# inverter_module.net
KiCad netlist of a schematic drawn in Altium Designer
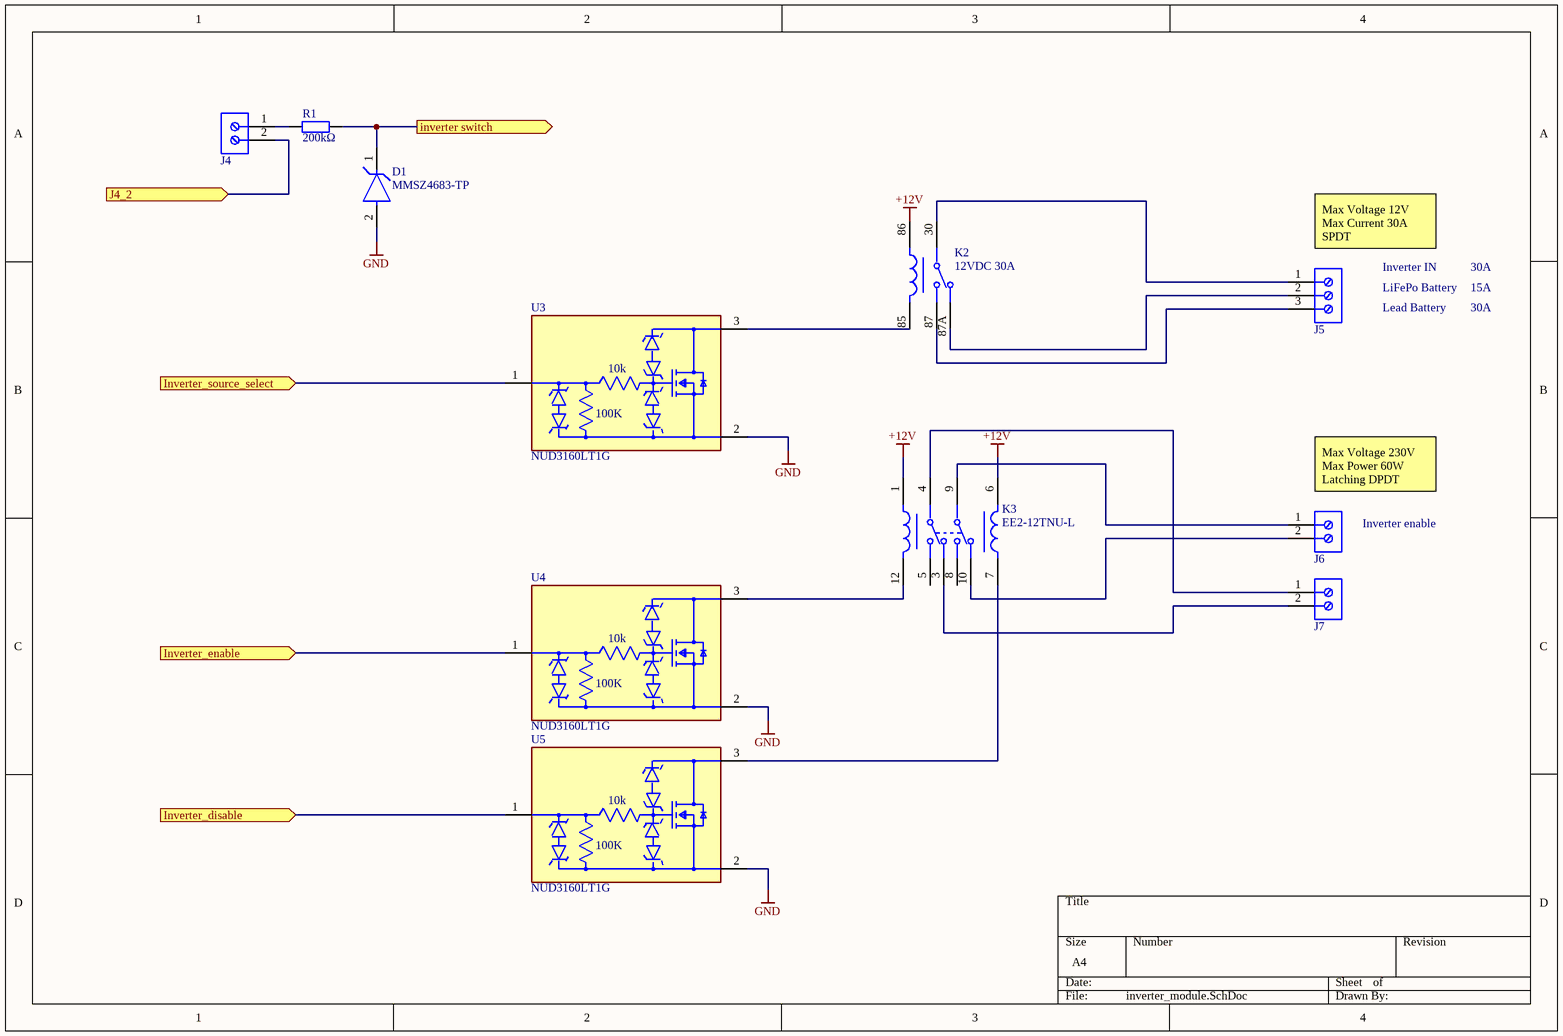
[diagram p0: inverter_module.SchDoc]

(export (version "E")
  (design (tool "Eeschema 10.0.6"))
  (components
    (comp (ref "D1")
      (value "MMSZ4683-TP")
      (footprint "FP-SOD-123-MFG")
      (description "DIODE ZENER 3V 500MW SOD123")
      (fields (field (name "TOLERANCE") "5%"))
      (libsource (lib "Altium Content Vault") (part "f813f71cba58e380607f5dd3caf9714"))
    )
    (comp (ref "J4")
      (value "282836-2")
      (footprint "TECO-282836-2_V")
      (description "Female Header, Pitch 5 mm, 1 x 2 Position, Height 10 mm, Tail Length 3.5 mm, Rohs, Bulk")
      (fields (field (name "VOLTAGE") "300V") (field (name "MANUFACTURER") "TE Connectivity"))
      (libsource (lib "Altium Content Vault") (part "CN-1P-F-TB2"))
    )
    (comp (ref "J5")
      (value "282836-3")
      (footprint "TE_282836-3")
      (description "Connector, Terminal Block; Wire Receptacle; 3 Pos.; 16-30 AWG; 0.197 in. CL; Sid")
      (fields (field (name "MANUFACTURER") "TE Connectivity") (field (name "VOLTAGE") "300V"))
      (libsource (lib "Schlib") (part "282836-3"))
    )
    (comp (ref "J6")
      (value "282836-2")
      (footprint "TECO-282836-2_V")
      (description "Female Header, Pitch 5 mm, 1 x 2 Position, Height 10 mm, Tail Length 3.5 mm, Rohs, Bulk")
      (fields (field (name "VOLTAGE") "300V") (field (name "MANUFACTURER") "TE Connectivity"))
      (libsource (lib "Altium Content Vault") (part "CN-1P-F-TB2"))
    )
    (comp (ref "J7")
      (value "282836-2")
      (footprint "TECO-282836-2_V")
      (description "Female Header, Pitch 5 mm, 1 x 2 Position, Height 10 mm, Tail Length 3.5 mm, Rohs, Bulk")
      (fields (field (name "VOLTAGE") "300V") (field (name "MANUFACTURER") "TE Connectivity"))
      (libsource (lib "Altium Content Vault") (part "CN-1P-F-TB2"))
    )
    (comp (ref "K2")
      (value "12VDC 30A")
      (footprint "automotive_relay")
      (description "Power Relay 12VDC 90(NO)/30(NC)A SPDT(26.5x26.5x24.5)mm Plug-In")
      (fields
        (field (name "MANUFACTURER") "TE Connectivity")
        (field (name "MANUFACTURER PART NUMBER") "1432787-1")
      )
      (libsource (lib "Schlib") (part "Relay automotive"))
    )
    (comp (ref "K3")
      (value "EE2-12TNU-L")
      (footprint "FP-EE2-12TNU-L-MFG")
      (description "RELAY GEN PURPOSE DPDT 2A 12VDC")
      (libsource (lib "Altium Content Vault") (part "a2c4c419374dacc8730513353986d3a"))
    )
    (comp (ref "R1")
      (value "200kΩ")
      (footprint "RESC2013X50X30ML20T20")
      (description "Resistor")
      (libsource (lib "PCB_Project") (part "Res_0805"))
    )
    (comp (ref "U3")
      (value "NUD3160LT1G")
      (footprint "FP-318-08-MFG")
      (description "IC INDCT LOAD DRVR INDUST SOT23")
      (fields
        (field (name "OCTOPART") "https://octopart.com/nud3160lt1g-on+semiconductor-470723")
        (field (name "MANUFACTURER") "ON Semiconductor")
      )
      (libsource (lib "Altium Content Vault") (part "3565ae214b0a124fee97343a38643ca"))
    )
    (comp (ref "U4")
      (value "NUD3160LT1G")
      (footprint "FP-318-08-MFG")
      (description "IC INDCT LOAD DRVR INDUST SOT23")
      (fields
        (field (name "OCTOPART") "https://octopart.com/nud3160lt1g-on+semiconductor-470723")
        (field (name "MANUFACTURER") "ON Semiconductor")
      )
      (libsource (lib "Altium Content Vault") (part "3565ae214b0a124fee97343a38643ca"))
    )
    (comp (ref "U5")
      (value "NUD3160LT1G")
      (footprint "FP-318-08-MFG")
      (description "IC INDCT LOAD DRVR INDUST SOT23")
      (fields
        (field (name "OCTOPART") "https://octopart.com/nud3160lt1g-on+semiconductor-470723")
        (field (name "MANUFACTURER") "ON Semiconductor")
      )
      (libsource (lib "Altium Content Vault") (part "3565ae214b0a124fee97343a38643ca"))
    )
  )
  (nets
    (net (code "1") (name "+12V") (class "Default")
      (node (ref "K2") (pin "86") (pinfunction "86_86") (pintype "passive"))
      (node (ref "K3") (pin "1") (pinfunction "SET+_1") (pintype "passive"))
      (node (ref "K3") (pin "6") (pinfunction "RESET+_6") (pintype "passive"))
    )
    (net (code "2") (name "/Inverter_disable") (class "Default")
      (node (ref "U5") (pin "1") (pinfunction "Gate_1") (pintype "passive"))
    )
    (net (code "3") (name "/Inverter_enable") (class "Default")
      (node (ref "U4") (pin "1") (pinfunction "Gate_1") (pintype "passive"))
    )
    (net (code "4") (name "/Inverter_source_select") (class "Default")
      (node (ref "U3") (pin "1") (pinfunction "Gate_1") (pintype "passive"))
    )
    (net (code "5") (name "/J4_2") (class "Default")
      (node (ref "J4") (pin "2") (pinfunction "2_2") (pintype "passive"))
    )
    (net (code "6") (name "/inverter switch") (class "Default")
      (node (ref "D1") (pin "1") (pinfunction "C_1") (pintype "passive"))
      (node (ref "R1") (pin "1") (pinfunction "1_1") (pintype "passive"))
    )
    (net (code "7") (name "GND") (class "Default")
      (node (ref "D1") (pin "2") (pinfunction "A_2") (pintype "passive"))
      (node (ref "U3") (pin "2") (pinfunction "Source_2") (pintype "passive"))
      (node (ref "U4") (pin "2") (pinfunction "Source_2") (pintype "passive"))
      (node (ref "U5") (pin "2") (pinfunction "Source_2") (pintype "passive"))
    )
    (net (code "8") (name "Net-(J4-Pad1)") (class "Default")
      (node (ref "J4") (pin "1") (pinfunction "1_1") (pintype "passive"))
      (node (ref "R1") (pin "2") (pinfunction "2_2") (pintype "passive"))
    )
    (net (code "9") (name "Net-(J5-Pad1)") (class "Default")
      (node (ref "J5") (pin "1") (pinfunction "1_1") (pintype "passive"))
      (node (ref "K2") (pin "30") (pinfunction "30_30") (pintype "passive"))
    )
    (net (code "10") (name "Net-(J5-Pad2)") (class "Default")
      (node (ref "J5") (pin "2") (pinfunction "2_2") (pintype "passive"))
      (node (ref "K2") (pin "87A") (pinfunction "87_87A") (pintype "passive"))
    )
    (net (code "11") (name "Net-(J5-Pad3)") (class "Default")
      (node (ref "J5") (pin "3") (pinfunction "3_3") (pintype "passive"))
      (node (ref "K2") (pin "87") (pinfunction "87_87") (pintype "passive"))
    )
    (net (code "12") (name "Net-(J6-Pad1)") (class "Default")
      (node (ref "J6") (pin "1") (pinfunction "1_1") (pintype "passive"))
      (node (ref "K3") (pin "9") (pinfunction "9_9") (pintype "passive"))
    )
    (net (code "13") (name "Net-(J6-Pad2)") (class "Default")
      (node (ref "J6") (pin "2") (pinfunction "2_2") (pintype "passive"))
      (node (ref "K3") (pin "10") (pinfunction "10_10") (pintype "passive"))
    )
    (net (code "14") (name "Net-(J7-Pad1)") (class "Default")
      (node (ref "J7") (pin "1") (pinfunction "1_1") (pintype "passive"))
      (node (ref "K3") (pin "4") (pinfunction "4_4") (pintype "passive"))
    )
    (net (code "15") (name "Net-(J7-Pad2)") (class "Default")
      (node (ref "J7") (pin "2") (pinfunction "2_2") (pintype "passive"))
      (node (ref "K3") (pin "3") (pinfunction "3_3") (pintype "passive"))
    )
    (net (code "16") (name "Net-(K3-RESET-)") (class "Default")
      (node (ref "K3") (pin "7") (pinfunction "RESET-_7") (pintype "passive"))
      (node (ref "U5") (pin "3") (pinfunction "Drain_3") (pintype "passive"))
    )
    (net (code "17") (name "Net-(K3-SET-)") (class "Default")
      (node (ref "K3") (pin "12") (pinfunction "SET-_12") (pintype "passive"))
      (node (ref "U4") (pin "3") (pinfunction "Drain_3") (pintype "passive"))
    )
    (net (code "18") (name "Net-(U3-Drain)") (class "Default")
      (node (ref "K2") (pin "85") (pinfunction "85_85") (pintype "passive"))
      (node (ref "U3") (pin "3") (pinfunction "Drain_3") (pintype "passive"))
    )
    (net (code "19") (name "unconnected-(K3-Pad5)") (class "Default")
      (node (ref "K3") (pin "5") (pinfunction "5_5") (pintype "passive"))
    )
    (net (code "20") (name "unconnected-(K3-Pad8)") (class "Default")
      (node (ref "K3") (pin "8") (pinfunction "8_8") (pintype "passive"))
    )
  )
)
